# switches.net
KiCad netlist of a schematic drawn in EAGLE
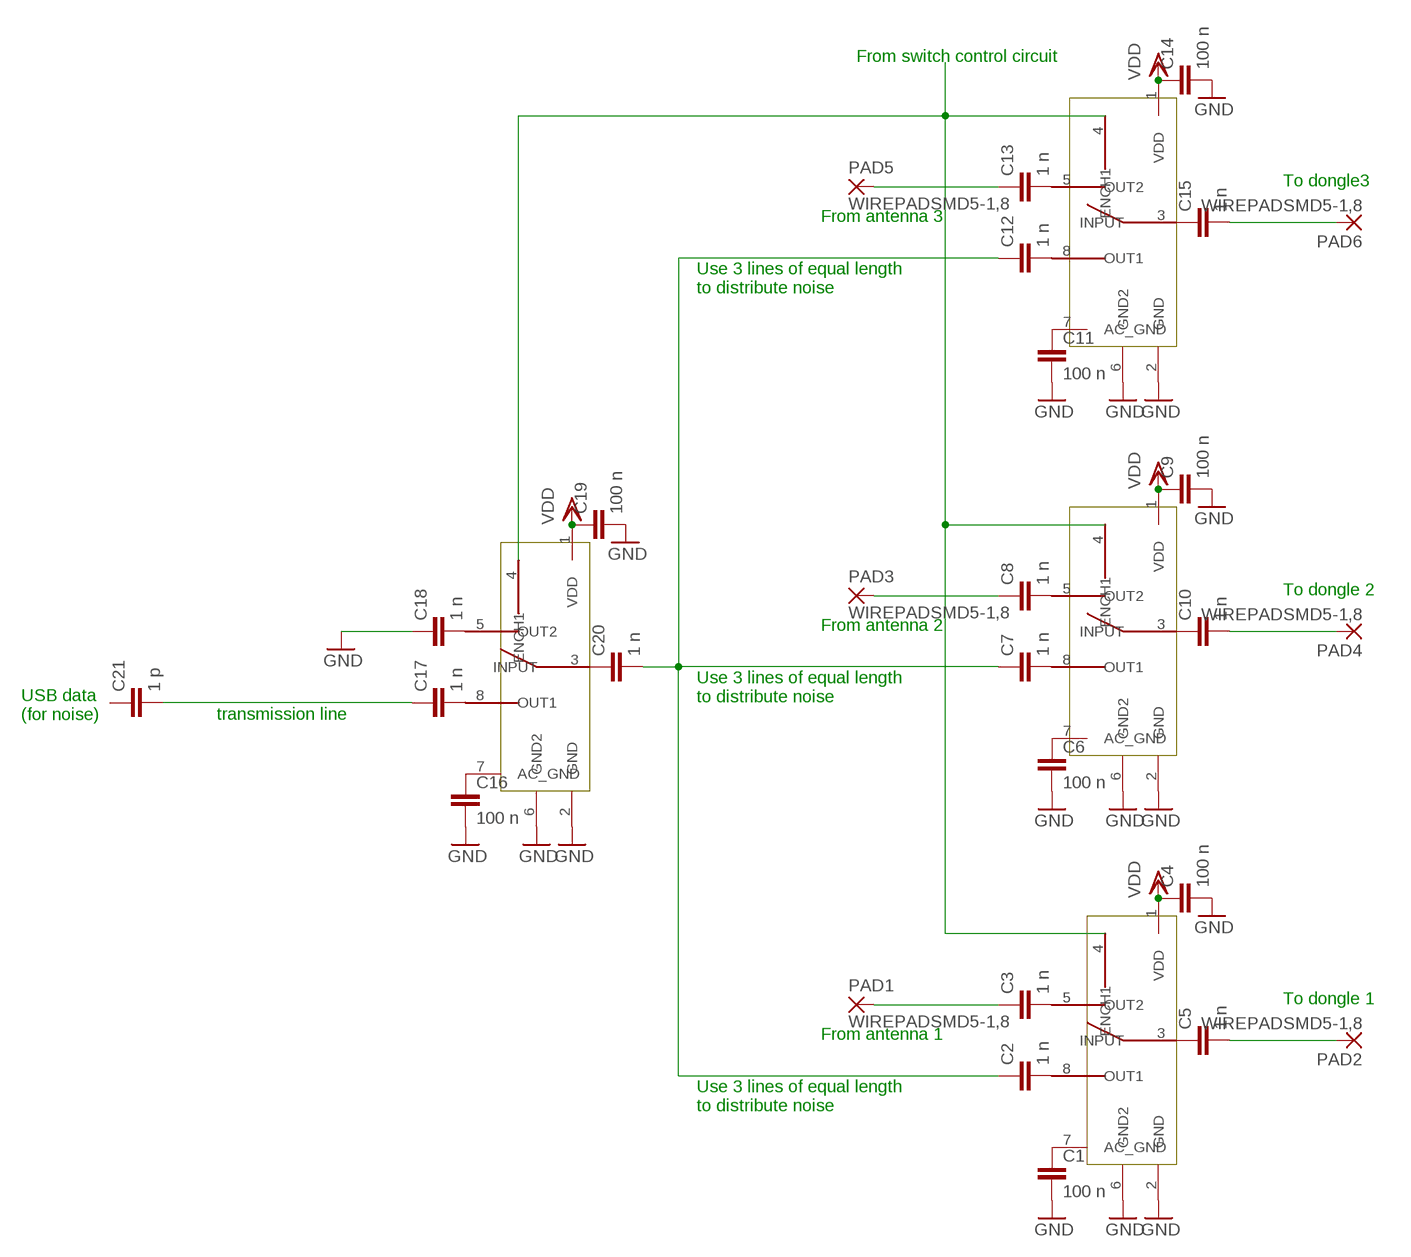
[diagram p0: schematic, sheet 1]

(export (version "E")
  (design (tool "Eeschema 10.0.6"))
  (components
    (comp (ref "C1")
      (value "100 n")
      (footprint "eagle-import:C0805")
      (libsource (lib "eagle-import") (part "C-EUC0805"))
    )
    (comp (ref "C2")
      (value "1 n")
      (footprint "eagle-import:C0805")
      (libsource (lib "eagle-import") (part "C-EUC0805"))
    )
    (comp (ref "C3")
      (value "1 n")
      (footprint "eagle-import:C0805")
      (libsource (lib "eagle-import") (part "C-EUC0805"))
    )
    (comp (ref "C4")
      (value "100 n")
      (footprint "eagle-import:C0805")
      (libsource (lib "eagle-import") (part "C-EUC0805"))
    )
    (comp (ref "C5")
      (value "1 n")
      (footprint "eagle-import:C0805")
      (libsource (lib "eagle-import") (part "C-EUC0805"))
    )
    (comp (ref "C6")
      (value "100 n")
      (footprint "eagle-import:C0805")
      (libsource (lib "eagle-import") (part "C-EUC0805"))
    )
    (comp (ref "C7")
      (value "1 n")
      (footprint "eagle-import:C0805")
      (libsource (lib "eagle-import") (part "C-EUC0805"))
    )
    (comp (ref "C8")
      (value "1 n")
      (footprint "eagle-import:C0805")
      (libsource (lib "eagle-import") (part "C-EUC0805"))
    )
    (comp (ref "C9")
      (value "100 n")
      (footprint "eagle-import:C0805")
      (libsource (lib "eagle-import") (part "C-EUC0805"))
    )
    (comp (ref "C10")
      (value "1 n")
      (footprint "eagle-import:C0805")
      (libsource (lib "eagle-import") (part "C-EUC0805"))
    )
    (comp (ref "C11")
      (value "100 n")
      (footprint "eagle-import:C0805")
      (libsource (lib "eagle-import") (part "C-EUC0805"))
    )
    (comp (ref "C12")
      (value "1 n")
      (footprint "eagle-import:C0805")
      (libsource (lib "eagle-import") (part "C-EUC0805"))
    )
    (comp (ref "C13")
      (value "1 n")
      (footprint "eagle-import:C0805")
      (libsource (lib "eagle-import") (part "C-EUC0805"))
    )
    (comp (ref "C14")
      (value "100 n")
      (footprint "eagle-import:C0805")
      (libsource (lib "eagle-import") (part "C-EUC0805"))
    )
    (comp (ref "C15")
      (value "1 n")
      (footprint "eagle-import:C0805")
      (libsource (lib "eagle-import") (part "C-EUC0805"))
    )
    (comp (ref "C16")
      (value "100 n")
      (footprint "eagle-import:C0805")
      (libsource (lib "eagle-import") (part "C-EUC0805"))
    )
    (comp (ref "C17")
      (value "1 n")
      (footprint "eagle-import:C0805")
      (libsource (lib "eagle-import") (part "C-EUC0805"))
    )
    (comp (ref "C18")
      (value "1 n")
      (footprint "eagle-import:C0805")
      (libsource (lib "eagle-import") (part "C-EUC0805"))
    )
    (comp (ref "C19")
      (value "100 n")
      (footprint "eagle-import:C0805")
      (libsource (lib "eagle-import") (part "C-EUC0805"))
    )
    (comp (ref "C20")
      (value "1 n")
      (footprint "eagle-import:C0805")
      (libsource (lib "eagle-import") (part "C-EUC0805"))
    )
    (comp (ref "C21")
      (value "1 p")
      (footprint "eagle-import:C0805")
      (libsource (lib "eagle-import") (part "C-EUC0805"))
    )
    (comp (ref "PAD1")
      (value "WIREPADSMD5-1,8")
      (footprint "eagle-import:5-1,8")
      (libsource (lib "eagle-import") (part "WIREPADSMD5-1,8"))
    )
    (comp (ref "PAD2")
      (value "WIREPADSMD5-1,8")
      (footprint "eagle-import:5-1,8")
      (libsource (lib "eagle-import") (part "WIREPADSMD5-1,8"))
    )
    (comp (ref "PAD3")
      (value "WIREPADSMD5-1,8")
      (footprint "eagle-import:5-1,8")
      (libsource (lib "eagle-import") (part "WIREPADSMD5-1,8"))
    )
    (comp (ref "PAD4")
      (value "WIREPADSMD5-1,8")
      (footprint "eagle-import:5-1,8")
      (libsource (lib "eagle-import") (part "WIREPADSMD5-1,8"))
    )
    (comp (ref "PAD5")
      (value "WIREPADSMD5-1,8")
      (footprint "eagle-import:5-1,8")
      (libsource (lib "eagle-import") (part "WIREPADSMD5-1,8"))
    )
    (comp (ref "PAD6")
      (value "WIREPADSMD5-1,8")
      (footprint "eagle-import:5-1,8")
      (libsource (lib "eagle-import") (part "WIREPADSMD5-1,8"))
    )
    (comp (ref "U$1")
      (value "SA630")
      (footprint "eagle-import:SOIC8")
      (libsource (lib "eagle-import") (part "SA630"))
    )
    (comp (ref "U$2")
      (value "SA630")
      (footprint "eagle-import:SOIC8")
      (libsource (lib "eagle-import") (part "SA630"))
    )
    (comp (ref "U$3")
      (value "SA630")
      (footprint "eagle-import:SOIC8")
      (libsource (lib "eagle-import") (part "SA630"))
    )
    (comp (ref "U$4")
      (value "SA630")
      (footprint "eagle-import:SOIC8")
      (libsource (lib "eagle-import") (part "SA630"))
    )
  )
  (nets
    (net (code "1") (name "GND") (class "Default")
      (node (ref "C1") (pin "2") (pinfunction "2_2") (pintype "passive"))
      (node (ref "C11") (pin "2") (pinfunction "2_2") (pintype "passive"))
      (node (ref "C14") (pin "2") (pinfunction "2_2") (pintype "passive"))
      (node (ref "C16") (pin "2") (pinfunction "2_2") (pintype "passive"))
      (node (ref "C18") (pin "1") (pinfunction "1_1") (pintype "passive"))
      (node (ref "C19") (pin "2") (pinfunction "2_2") (pintype "passive"))
      (node (ref "C4") (pin "2") (pinfunction "2_2") (pintype "passive"))
      (node (ref "C6") (pin "2") (pinfunction "2_2") (pintype "passive"))
      (node (ref "C9") (pin "2") (pinfunction "2_2") (pintype "passive"))
      (node (ref "U$1") (pin "2") (pinfunction "GND_2") (pintype "bidirectional"))
      (node (ref "U$1") (pin "6") (pinfunction "GND2_6") (pintype "bidirectional"))
      (node (ref "U$2") (pin "2") (pinfunction "GND_2") (pintype "bidirectional"))
      (node (ref "U$2") (pin "6") (pinfunction "GND2_6") (pintype "bidirectional"))
      (node (ref "U$3") (pin "2") (pinfunction "GND_2") (pintype "bidirectional"))
      (node (ref "U$3") (pin "6") (pinfunction "GND2_6") (pintype "bidirectional"))
      (node (ref "U$4") (pin "2") (pinfunction "GND_2") (pintype "bidirectional"))
      (node (ref "U$4") (pin "6") (pinfunction "GND2_6") (pintype "bidirectional"))
    )
    (net (code "2") (name "Net-(C12-Pad1)") (class "Default")
      (node (ref "C12") (pin "1") (pinfunction "1_1") (pintype "passive"))
      (node (ref "C2") (pin "1") (pinfunction "1_1") (pintype "passive"))
      (node (ref "C20") (pin "2") (pinfunction "2_2") (pintype "passive"))
      (node (ref "C7") (pin "1") (pinfunction "1_1") (pintype "passive"))
    )
    (net (code "3") (name "Net-(C17-Pad1)") (class "Default")
      (node (ref "C17") (pin "1") (pinfunction "1_1") (pintype "passive"))
      (node (ref "C21") (pin "2") (pinfunction "2_2") (pintype "passive"))
    )
    (net (code "4") (name "Net-(PAD1-P)") (class "Default")
      (node (ref "C3") (pin "1") (pinfunction "1_1") (pintype "passive"))
      (node (ref "PAD1") (pin "1") (pinfunction "P_1") (pintype "passive"))
    )
    (net (code "5") (name "Net-(PAD2-P)") (class "Default")
      (node (ref "C5") (pin "2") (pinfunction "2_2") (pintype "passive"))
      (node (ref "PAD2") (pin "1") (pinfunction "P_1") (pintype "passive"))
    )
    (net (code "6") (name "Net-(PAD3-P)") (class "Default")
      (node (ref "C8") (pin "1") (pinfunction "1_1") (pintype "passive"))
      (node (ref "PAD3") (pin "1") (pinfunction "P_1") (pintype "passive"))
    )
    (net (code "7") (name "Net-(PAD4-P)") (class "Default")
      (node (ref "C10") (pin "2") (pinfunction "2_2") (pintype "passive"))
      (node (ref "PAD4") (pin "1") (pinfunction "P_1") (pintype "passive"))
    )
    (net (code "8") (name "Net-(PAD5-P)") (class "Default")
      (node (ref "C13") (pin "1") (pinfunction "1_1") (pintype "passive"))
      (node (ref "PAD5") (pin "1") (pinfunction "P_1") (pintype "passive"))
    )
    (net (code "9") (name "Net-(PAD6-P)") (class "Default")
      (node (ref "C15") (pin "2") (pinfunction "2_2") (pintype "passive"))
      (node (ref "PAD6") (pin "1") (pinfunction "P_1") (pintype "passive"))
    )
    (net (code "10") (name "Net-(U$1-AC_GND)") (class "Default")
      (node (ref "C1") (pin "1") (pinfunction "1_1") (pintype "passive"))
      (node (ref "U$1") (pin "7") (pinfunction "AC_GND_7") (pintype "bidirectional"))
    )
    (net (code "11") (name "Net-(U$1-ENCH1)") (class "Default")
      (node (ref "U$1") (pin "4") (pinfunction "ENCH1_4") (pintype "input"))
      (node (ref "U$2") (pin "4") (pinfunction "ENCH1_4") (pintype "input"))
      (node (ref "U$3") (pin "4") (pinfunction "ENCH1_4") (pintype "input"))
      (node (ref "U$4") (pin "4") (pinfunction "ENCH1_4") (pintype "input"))
    )
    (net (code "12") (name "Net-(U$1-INPUT)") (class "Default")
      (node (ref "C5") (pin "1") (pinfunction "1_1") (pintype "passive"))
      (node (ref "U$1") (pin "3") (pinfunction "INPUT_3") (pintype "bidirectional"))
    )
    (net (code "13") (name "Net-(U$1-OUT1)") (class "Default")
      (node (ref "C2") (pin "2") (pinfunction "2_2") (pintype "passive"))
      (node (ref "U$1") (pin "8") (pinfunction "OUT1_8") (pintype "bidirectional"))
    )
    (net (code "14") (name "Net-(U$1-OUT2)") (class "Default")
      (node (ref "C3") (pin "2") (pinfunction "2_2") (pintype "passive"))
      (node (ref "U$1") (pin "5") (pinfunction "OUT2_5") (pintype "bidirectional"))
    )
    (net (code "15") (name "Net-(U$2-AC_GND)") (class "Default")
      (node (ref "C6") (pin "1") (pinfunction "1_1") (pintype "passive"))
      (node (ref "U$2") (pin "7") (pinfunction "AC_GND_7") (pintype "bidirectional"))
    )
    (net (code "16") (name "Net-(U$2-INPUT)") (class "Default")
      (node (ref "C10") (pin "1") (pinfunction "1_1") (pintype "passive"))
      (node (ref "U$2") (pin "3") (pinfunction "INPUT_3") (pintype "bidirectional"))
    )
    (net (code "17") (name "Net-(U$2-OUT1)") (class "Default")
      (node (ref "C7") (pin "2") (pinfunction "2_2") (pintype "passive"))
      (node (ref "U$2") (pin "8") (pinfunction "OUT1_8") (pintype "bidirectional"))
    )
    (net (code "18") (name "Net-(U$2-OUT2)") (class "Default")
      (node (ref "C8") (pin "2") (pinfunction "2_2") (pintype "passive"))
      (node (ref "U$2") (pin "5") (pinfunction "OUT2_5") (pintype "bidirectional"))
    )
    (net (code "19") (name "Net-(U$3-AC_GND)") (class "Default")
      (node (ref "C11") (pin "1") (pinfunction "1_1") (pintype "passive"))
      (node (ref "U$3") (pin "7") (pinfunction "AC_GND_7") (pintype "bidirectional"))
    )
    (net (code "20") (name "Net-(U$3-INPUT)") (class "Default")
      (node (ref "C15") (pin "1") (pinfunction "1_1") (pintype "passive"))
      (node (ref "U$3") (pin "3") (pinfunction "INPUT_3") (pintype "bidirectional"))
    )
    (net (code "21") (name "Net-(U$3-OUT1)") (class "Default")
      (node (ref "C12") (pin "2") (pinfunction "2_2") (pintype "passive"))
      (node (ref "U$3") (pin "8") (pinfunction "OUT1_8") (pintype "bidirectional"))
    )
    (net (code "22") (name "Net-(U$3-OUT2)") (class "Default")
      (node (ref "C13") (pin "2") (pinfunction "2_2") (pintype "passive"))
      (node (ref "U$3") (pin "5") (pinfunction "OUT2_5") (pintype "bidirectional"))
    )
    (net (code "23") (name "Net-(U$4-AC_GND)") (class "Default")
      (node (ref "C16") (pin "1") (pinfunction "1_1") (pintype "passive"))
      (node (ref "U$4") (pin "7") (pinfunction "AC_GND_7") (pintype "bidirectional"))
    )
    (net (code "24") (name "Net-(U$4-INPUT)") (class "Default")
      (node (ref "C20") (pin "1") (pinfunction "1_1") (pintype "passive"))
      (node (ref "U$4") (pin "3") (pinfunction "INPUT_3") (pintype "bidirectional"))
    )
    (net (code "25") (name "Net-(U$4-OUT1)") (class "Default")
      (node (ref "C17") (pin "2") (pinfunction "2_2") (pintype "passive"))
      (node (ref "U$4") (pin "8") (pinfunction "OUT1_8") (pintype "bidirectional"))
    )
    (net (code "26") (name "Net-(U$4-OUT2)") (class "Default")
      (node (ref "C18") (pin "2") (pinfunction "2_2") (pintype "passive"))
      (node (ref "U$4") (pin "5") (pinfunction "OUT2_5") (pintype "bidirectional"))
    )
    (net (code "27") (name "VDD") (class "Default")
      (node (ref "C14") (pin "1") (pinfunction "1_1") (pintype "passive"))
      (node (ref "C19") (pin "1") (pinfunction "1_1") (pintype "passive"))
      (node (ref "C4") (pin "1") (pinfunction "1_1") (pintype "passive"))
      (node (ref "C9") (pin "1") (pinfunction "1_1") (pintype "passive"))
      (node (ref "U$1") (pin "1") (pinfunction "VDD_1") (pintype "bidirectional"))
      (node (ref "U$2") (pin "1") (pinfunction "VDD_1") (pintype "bidirectional"))
      (node (ref "U$3") (pin "1") (pinfunction "VDD_1") (pintype "bidirectional"))
      (node (ref "U$4") (pin "1") (pinfunction "VDD_1") (pintype "bidirectional"))
    )
    (net (code "28") (name "unconnected-(C21-Pad1)") (class "Default")
      (node (ref "C21") (pin "1") (pinfunction "1_1") (pintype "passive"))
    )
  )
)
